# FeatherRTC.net
KiCad netlist of a schematic drawn in EAGLE
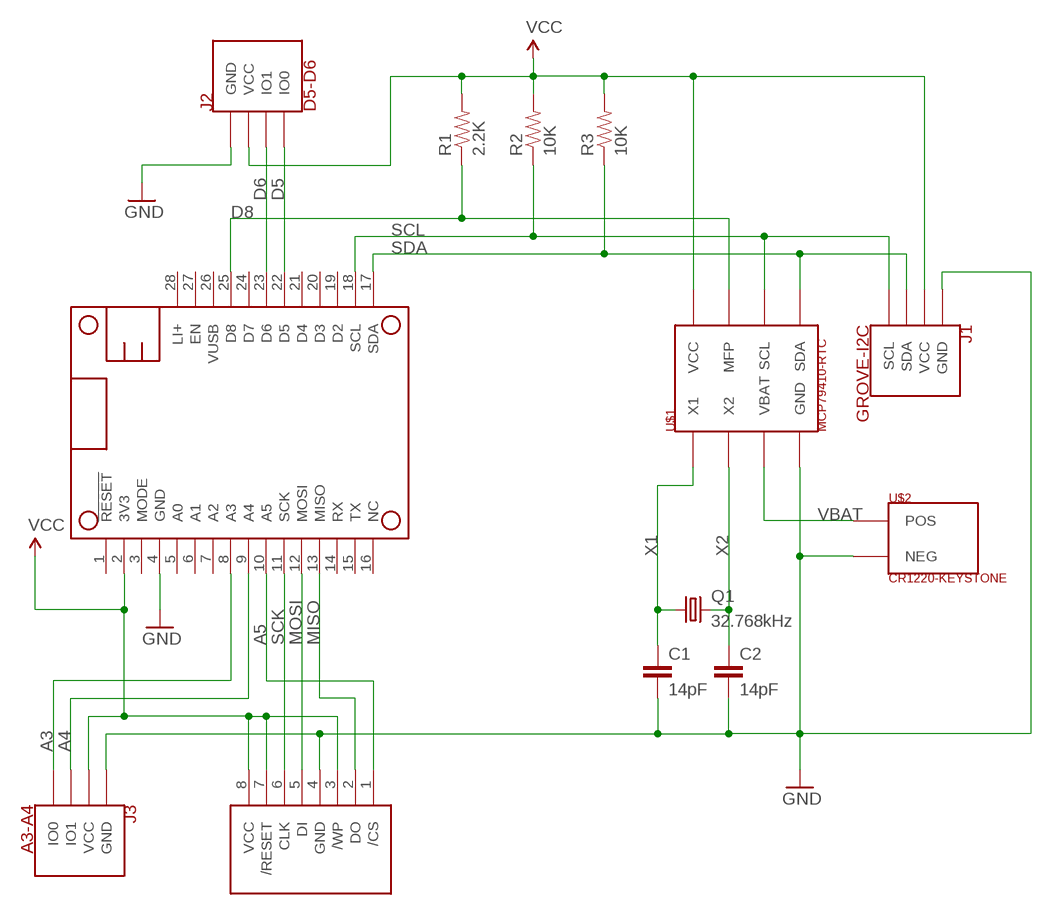
[diagram p0: schematic, sheet 1]

(export (version "E")
  (design (tool "Eeschema 10.0.6"))
  (components
    (comp (ref "C1")
      (value "14pF")
      (footprint "eagle-import:0603-CAP")
      (libsource (lib "eagle-import") (part "CAP-14PF-0603"))
    )
    (comp (ref "C2")
      (value "14pF")
      (footprint "eagle-import:0603-CAP")
      (libsource (lib "eagle-import") (part "CAP-14PF-0603"))
    )
    (comp (ref "J1")
      (value "GROVE-I2C")
      (footprint "eagle-import:GROVE-VERT-PTH")
      (libsource (lib "eagle-import") (part "GROVE-I2C"))
    )
    (comp (ref "J2")
      (value "D5-D6")
      (footprint "eagle-import:GROVE-VERT-PTH")
      (libsource (lib "eagle-import") (part "GROVE-IO"))
    )
    (comp (ref "J3")
      (value "A3-A4")
      (footprint "eagle-import:GROVE-VERT-PTH")
      (libsource (lib "eagle-import") (part "GROVE-IO"))
    )
    (comp (ref "MS1")
      (value "FEATHERWING_NODIM")
      (footprint "eagle-import:FEATHERWING_NODIM")
      (libsource (lib "eagle-import") (part "FEATHERWING_NODIM"))
    )
    (comp (ref "Q1")
      (value "32.768kHz")
      (footprint "eagle-import:FC-135")
      (libsource (lib "eagle-import") (part "FC-135-CRYSTAL"))
    )
    (comp (ref "R1")
      (value "2.2K")
      (footprint "eagle-import:0805")
      (libsource (lib "eagle-import") (part "RES-2K2-0805"))
    )
    (comp (ref "R2")
      (value "10K")
      (footprint "eagle-import:0603-RES")
      (libsource (lib "eagle-import") (part "RES-10K-06030603"))
    )
    (comp (ref "R3")
      (value "10K")
      (footprint "eagle-import:0603-RES")
      (libsource (lib "eagle-import") (part "RES-10K-06030603"))
    )
    (comp (ref "U$1")
      (value "MCP79410-RTC")
      (footprint "eagle-import:8-SOIC-MICROCHIP-3.9")
      (libsource (lib "eagle-import") (part "MCP79410-RTC"))
    )
    (comp (ref "U$2")
      (value "CR1220-KEYSTONE")
      (footprint "eagle-import:CR1220-KEYSTONE")
      (libsource (lib "eagle-import") (part "CR1220-KEYSTONE"))
    )
    (comp (ref "U$3")
      (value "W25Q-FLASH")
      (footprint "eagle-import:8-SOIC-WINBOND-208")
      (libsource (lib "eagle-import") (part "W25Q-FLASH"))
    )
  )
  (nets
    (net (code "1") (name "/A3") (class "Default")
      (node (ref "J3") (pin "1") (pinfunction "IO0_1") (pintype "passive"))
      (node (ref "MS1") (pin "8") (pinfunction "A3_8") (pintype "bidirectional"))
    )
    (net (code "2") (name "/A4") (class "Default")
      (node (ref "J3") (pin "2") (pinfunction "IO1_2") (pintype "passive"))
      (node (ref "MS1") (pin "9") (pinfunction "A4_9") (pintype "bidirectional"))
    )
    (net (code "3") (name "/A5") (class "Default")
      (node (ref "MS1") (pin "10") (pinfunction "A5_10") (pintype "bidirectional"))
      (node (ref "U$3") (pin "1") (pinfunction "/CS_1") (pintype "input"))
    )
    (net (code "4") (name "/D5") (class "Default")
      (node (ref "J2") (pin "1") (pinfunction "IO0_1") (pintype "passive"))
      (node (ref "MS1") (pin "22") (pinfunction "D5_22") (pintype "bidirectional"))
    )
    (net (code "5") (name "/D6") (class "Default")
      (node (ref "J2") (pin "2") (pinfunction "IO1_2") (pintype "passive"))
      (node (ref "MS1") (pin "23") (pinfunction "D6_23") (pintype "bidirectional"))
    )
    (net (code "6") (name "/D8") (class "Default")
      (node (ref "MS1") (pin "25") (pinfunction "D8_25") (pintype "bidirectional"))
      (node (ref "R1") (pin "1") (pinfunction "1_1") (pintype "passive"))
      (node (ref "U$1") (pin "7") (pinfunction "MFP_7") (pintype "output"))
    )
    (net (code "7") (name "/LI+") (class "Default")
      (node (ref "MS1") (pin "28") (pinfunction "LI+_28") (pintype "power_in"))
    )
    (net (code "8") (name "/MISO") (class "Default")
      (node (ref "MS1") (pin "13") (pinfunction "MISO_13") (pintype "bidirectional"))
      (node (ref "U$3") (pin "2") (pinfunction "DO_2") (pintype "output"))
    )
    (net (code "9") (name "/MOSI") (class "Default")
      (node (ref "MS1") (pin "12") (pinfunction "MOSI_12") (pintype "bidirectional"))
      (node (ref "U$3") (pin "5") (pinfunction "DI_5") (pintype "input"))
    )
    (net (code "10") (name "/SCK") (class "Default")
      (node (ref "MS1") (pin "11") (pinfunction "SCK_11") (pintype "bidirectional"))
      (node (ref "U$3") (pin "6") (pinfunction "CLK_6") (pintype "input"))
    )
    (net (code "11") (name "/SCL") (class "Default")
      (node (ref "J1") (pin "1") (pinfunction "SCL_1") (pintype "passive"))
      (node (ref "MS1") (pin "18") (pinfunction "SCL_18") (pintype "bidirectional"))
      (node (ref "R2") (pin "1") (pinfunction "1_1") (pintype "passive"))
      (node (ref "U$1") (pin "6") (pinfunction "SCL_6") (pintype "bidirectional"))
    )
    (net (code "12") (name "/SDA") (class "Default")
      (node (ref "J1") (pin "2") (pinfunction "SDA_2") (pintype "passive"))
      (node (ref "MS1") (pin "17") (pinfunction "SDA_17") (pintype "bidirectional"))
      (node (ref "R3") (pin "1") (pinfunction "1_1") (pintype "passive"))
      (node (ref "U$1") (pin "5") (pinfunction "SDA_5") (pintype "bidirectional"))
    )
    (net (code "13") (name "/VBAT") (class "Default")
      (node (ref "U$1") (pin "3") (pinfunction "VBAT_3") (pintype "power_in"))
      (node (ref "U$2") (pin "POS") (pinfunction "POS_POS") (pintype "passive"))
    )
    (net (code "14") (name "/VUSB") (class "Default")
      (node (ref "MS1") (pin "26") (pinfunction "VUSB_26") (pintype "power_in"))
    )
    (net (code "15") (name "/X1") (class "Default")
      (node (ref "C1") (pin "1") (pinfunction "1_1") (pintype "passive"))
      (node (ref "Q1") (pin "1") (pinfunction "1_1") (pintype "passive"))
      (node (ref "U$1") (pin "1") (pinfunction "X1_1") (pintype "passive"))
    )
    (net (code "16") (name "/X2") (class "Default")
      (node (ref "C2") (pin "1") (pinfunction "1_1") (pintype "passive"))
      (node (ref "Q1") (pin "2") (pinfunction "2_2") (pintype "passive"))
      (node (ref "U$1") (pin "2") (pinfunction "X2_2") (pintype "passive"))
    )
    (net (code "17") (name "GND") (class "Default")
      (node (ref "C1") (pin "2") (pinfunction "2_2") (pintype "passive"))
      (node (ref "C2") (pin "2") (pinfunction "2_2") (pintype "passive"))
      (node (ref "J1") (pin "4") (pinfunction "GND_4") (pintype "passive"))
      (node (ref "J2") (pin "4") (pinfunction "GND_4") (pintype "passive"))
      (node (ref "J3") (pin "4") (pinfunction "GND_4") (pintype "passive"))
      (node (ref "MS1") (pin "4") (pinfunction "GND_4") (pintype "power_in"))
      (node (ref "U$1") (pin "4") (pinfunction "GND_4") (pintype "passive"))
      (node (ref "U$2") (pin "NEG") (pinfunction "NEG_NEG") (pintype "passive"))
      (node (ref "U$3") (pin "4") (pinfunction "GND_4") (pintype "power_in"))
    )
    (net (code "18") (name "VCC") (class "Default")
      (node (ref "J1") (pin "3") (pinfunction "VCC_3") (pintype "passive"))
      (node (ref "J2") (pin "3") (pinfunction "VCC_3") (pintype "passive"))
      (node (ref "J3") (pin "3") (pinfunction "VCC_3") (pintype "passive"))
      (node (ref "MS1") (pin "2") (pinfunction "3V3_2") (pintype "power_in"))
      (node (ref "R1") (pin "2") (pinfunction "2_2") (pintype "passive"))
      (node (ref "R2") (pin "2") (pinfunction "2_2") (pintype "passive"))
      (node (ref "R3") (pin "2") (pinfunction "2_2") (pintype "passive"))
      (node (ref "U$1") (pin "8") (pinfunction "VCC_8") (pintype "power_in"))
      (node (ref "U$3") (pin "3") (pinfunction "/WP_3") (pintype "input"))
      (node (ref "U$3") (pin "7") (pinfunction "/RESET_7") (pintype "input"))
      (node (ref "U$3") (pin "8") (pinfunction "VCC_8") (pintype "power_in"))
    )
    (net (code "19") (name "unconnected-(MS1-A0-Pad5)") (class "Default")
      (node (ref "MS1") (pin "5") (pinfunction "A0_5") (pintype "bidirectional"))
    )
    (net (code "20") (name "unconnected-(MS1-A1-Pad6)") (class "Default")
      (node (ref "MS1") (pin "6") (pinfunction "A1_6") (pintype "bidirectional"))
    )
    (net (code "21") (name "unconnected-(MS1-A2-Pad7)") (class "Default")
      (node (ref "MS1") (pin "7") (pinfunction "A2_7") (pintype "bidirectional"))
    )
    (net (code "22") (name "unconnected-(MS1-D2-Pad19)") (class "Default")
      (node (ref "MS1") (pin "19") (pinfunction "D2_19") (pintype "bidirectional"))
    )
    (net (code "23") (name "unconnected-(MS1-D3-Pad20)") (class "Default")
      (node (ref "MS1") (pin "20") (pinfunction "D3_20") (pintype "bidirectional"))
    )
    (net (code "24") (name "unconnected-(MS1-D4-Pad21)") (class "Default")
      (node (ref "MS1") (pin "21") (pinfunction "D4_21") (pintype "bidirectional"))
    )
    (net (code "25") (name "unconnected-(MS1-D7-Pad24)") (class "Default")
      (node (ref "MS1") (pin "24") (pinfunction "D7_24") (pintype "bidirectional"))
    )
    (net (code "26") (name "unconnected-(MS1-EN-Pad27)") (class "Default")
      (node (ref "MS1") (pin "27") (pinfunction "EN_27") (pintype "passive"))
    )
    (net (code "27") (name "unconnected-(MS1-MODE-Pad3)") (class "Default")
      (node (ref "MS1") (pin "3") (pinfunction "MODE_3") (pintype "passive"))
    )
    (net (code "28") (name "unconnected-(MS1-NC-Pad16)") (class "Default")
      (node (ref "MS1") (pin "16") (pinfunction "NC_16") (pintype "passive"))
    )
    (net (code "29") (name "unconnected-(MS1-RX-Pad14)") (class "Default")
      (node (ref "MS1") (pin "14") (pinfunction "RX_14") (pintype "bidirectional"))
    )
    (net (code "30") (name "unconnected-(MS1-TX-Pad15)") (class "Default")
      (node (ref "MS1") (pin "15") (pinfunction "TX_15") (pintype "bidirectional"))
    )
    (net (code "31") (name "unconnected-(MS1-~{RESET}-Pad1)") (class "Default")
      (node (ref "MS1") (pin "1") (pinfunction "~{RESET}_1") (pintype "input"))
    )
  )
)
